# ife19_TS_AIL.net
KiCad netlist of a schematic drawn in Altium Designer
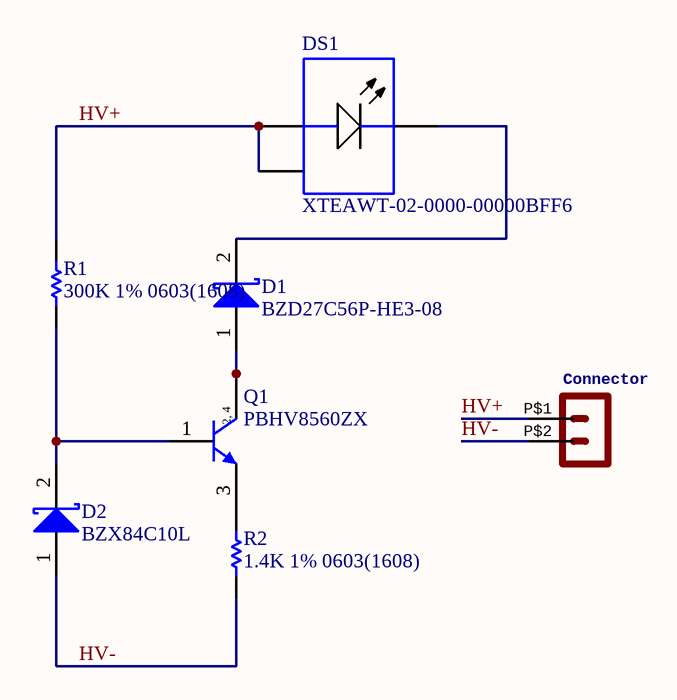
[diagram p0: ife19_TS_AIL.SchDoc]

(export (version "E")
  (design (tool "Eeschema 10.0.6"))
  (components
    (comp (ref "Connector")
      (value "~")
      (footprint "43650-0224")
      (libsource (lib "MOLEX Micro-Fit") (part "HEADER_POS2_?43650-0224"))
    )
    (comp (ref "D1")
      (value "BZD27C56P-HE3-08")
      (footprint "VISH-DO-219AB_V")
      (description "Schottky Rectifier, 30 V, 1.1 A, 2-Pin DO-219AB (SMF), RoHS, Tape and Reel")
      (fields (field (name "PARTNUMBER") "SL03-GS08CT") (field (name "MANUFACTURER") "Vishay Semiconductor"))
      (libsource (lib "Altium Content Vault") (part "DSKY-AK-2"))
    )
    (comp (ref "D2")
      (value "BZX84C10L")
      (footprint "VISH-DO-219AB_V")
      (description "Schottky Rectifier, 30 V, 1.1 A, 2-Pin DO-219AB (SMF), RoHS, Tape and Reel")
      (fields (field (name "PARTNUMBER") "SL03-GS08CT") (field (name "MANUFACTURER") "Vishay Semiconductor"))
      (libsource (lib "Altium Content Vault") (part "DSKY-AK-2"))
    )
    (comp (ref "DS1")
      (value "XTEAWT-02-0000-00000BFF6")
      (footprint "CREE-XT-E_LED-3_A_V")
      (description "XLamp(R) XT-E LED, 350 mA, 2.85 V, 3-Pin SMD, RoHS, Tape and Reel")
      (fields (field (name "MANUFACTURER") "Cree"))
      (libsource (lib "Altium Content Vault") (part "LED_WHITE-3"))
    )
    (comp (ref "Q1")
      (value "PBHV8560ZX")
      (footprint "NXP-SOT223_L")
      (description "NPN Medium Power Transistor, 60 V, 1 A, -55 to 150 degC, 4-Pin SOT223, RoHS, Tape and Reel")
      (fields (field (name "MANUFACTURER") "NXP Semiconductors"))
      (libsource (lib "Altium Content Vault") (part "BJT-NPN-BCEC-4"))
    )
    (comp (ref "R1")
      (value "300K 1% 0603(1608)")
      (footprint "RESC0603(1608)_L")
      (description "249K 0.1W 1% 0603 (1608 Metric)  SMD")
      (fields (field (name "POWER") "0.1 W") (field (name "TOLERANCE") "1 %"))
      (libsource (lib "Altium Content Vault") (part "RES"))
    )
    (comp (ref "R2")
      (value "1.4K 1% 0603(1608)")
      (footprint "RESC0603(1608)_L")
      (description "348K 0.1W 1% 0603 (1608 Metric)  SMD")
      (fields (field (name "TOLERANCE") "1 %") (field (name "POWER") "0.1 W"))
      (libsource (lib "Altium Content Vault") (part "RES"))
    )
  )
  (nets
    (net (code "1") (name "/HV+") (class "Default")
      (node (ref "Connector") (pin "P$1") (pinfunction "1_P$1") (pintype "passive"))
      (node (ref "DS1") (pin "1") (pinfunction "A_1") (pintype "passive"))
      (node (ref "DS1") (pin "3") (pinfunction "EP_3") (pintype "passive"))
      (node (ref "R1") (pin "2") (pinfunction "2_2") (pintype "passive"))
    )
    (net (code "2") (name "/HV-") (class "Default")
      (node (ref "Connector") (pin "P$2") (pinfunction "2_P$2") (pintype "passive"))
      (node (ref "D2") (pin "1") (pinfunction "A_1") (pintype "passive"))
      (node (ref "R2") (pin "1") (pinfunction "1_1") (pintype "passive"))
    )
    (net (code "3") (name "Net-(D1-A)") (class "Default")
      (node (ref "D1") (pin "1") (pinfunction "A_1") (pintype "passive"))
      (node (ref "Q1") (pin "2") (pinfunction "C_2") (pintype "passive"))
      (node (ref "Q1") (pin "4") (pinfunction "C_4") (pintype "passive"))
    )
    (net (code "4") (name "Net-(D1-K)") (class "Default")
      (node (ref "D1") (pin "2") (pinfunction "K_2") (pintype "passive"))
      (node (ref "DS1") (pin "2") (pinfunction "K_2") (pintype "passive"))
    )
    (net (code "5") (name "Net-(D2-K)") (class "Default")
      (node (ref "D2") (pin "2") (pinfunction "K_2") (pintype "passive"))
      (node (ref "Q1") (pin "1") (pinfunction "B_1") (pintype "passive"))
      (node (ref "R1") (pin "1") (pinfunction "1_1") (pintype "passive"))
    )
    (net (code "6") (name "Net-(Q1-E)") (class "Default")
      (node (ref "Q1") (pin "3") (pinfunction "E_3") (pintype "passive"))
      (node (ref "R2") (pin "2") (pinfunction "2_2") (pintype "passive"))
    )
  )
)
